# VOLTHAT.net
KiCad netlist of a schematic drawn in EAGLE
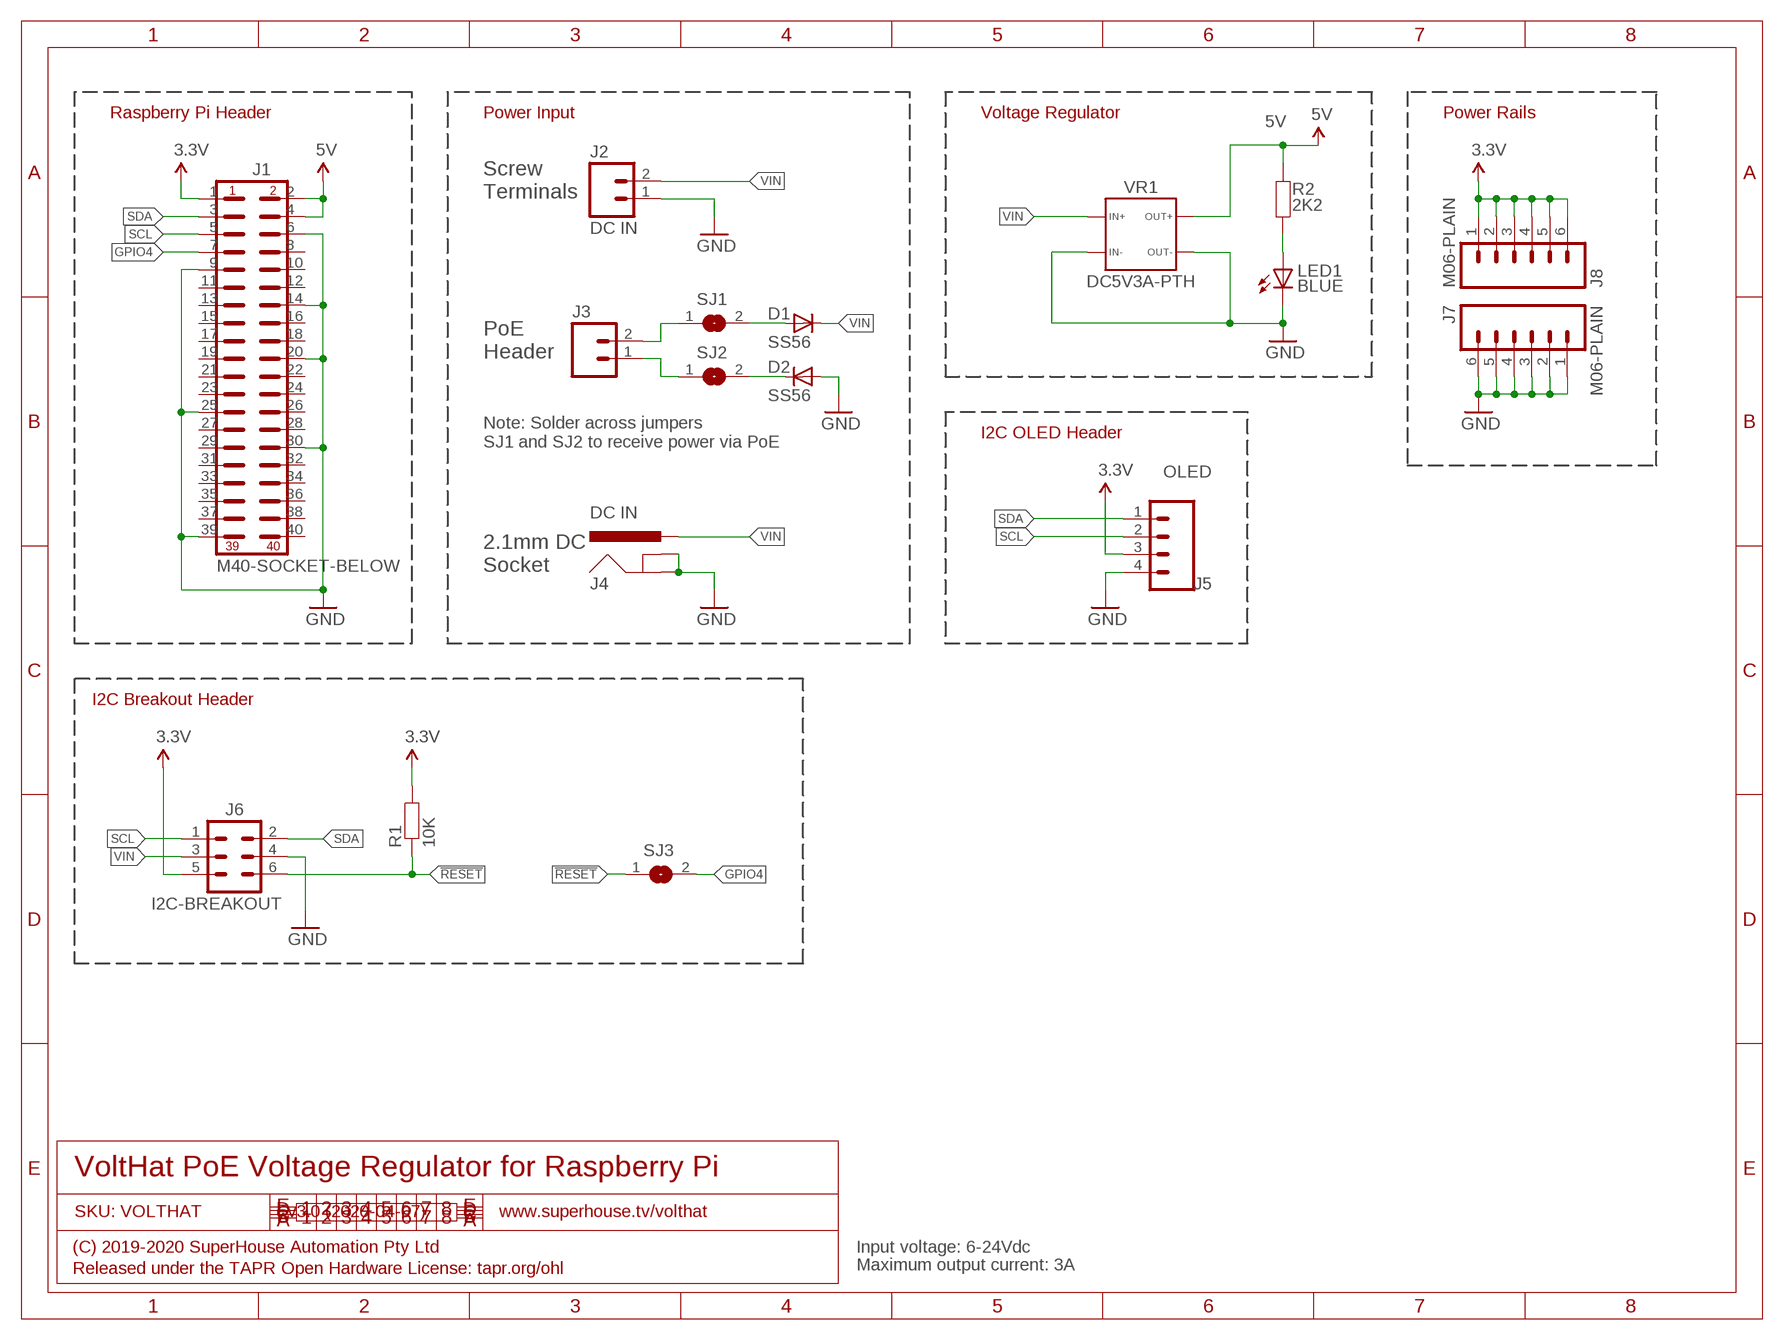
[diagram p0: schematic, sheet 1]

(export (version "E")
  (design (tool "Eeschema 10.0.6"))
  (components
    (comp (ref "D1")
      (value "SS56")
      (footprint "eagle-import:SMA-DIODE")
      (libsource (lib "eagle-import") (part "DIODESMA"))
    )
    (comp (ref "D2")
      (value "SS56")
      (footprint "eagle-import:SMA-DIODE")
      (libsource (lib "eagle-import") (part "DIODESMA"))
    )
    (comp (ref "J1")
      (value "M40-SOCKET-BELOW")
      (footprint "eagle-import:2X20-S-BELOW")
      (libsource (lib "eagle-import") (part "M40-SOCKET-BELOW"))
    )
    (comp (ref "J2")
      (value "DC IN")
      (footprint "eagle-import:SCREWTERMINAL-3.5MM-2")
      (libsource (lib "eagle-import") (part "M02-SCREW-3.5MM"))
    )
    (comp (ref "J3")
      (value "M02-SOCKET-BELOW")
      (footprint "eagle-import:1X02-S-BELOW")
      (libsource (lib "eagle-import") (part "M02-SOCKET-BELOW"))
    )
    (comp (ref "J4")
      (value "DC IN")
      (footprint "eagle-import:POWER_JACK_SLOTS")
      (libsource (lib "eagle-import") (part "POWER_JACK-SLOTS"))
    )
    (comp (ref "J5")
      (value "OLED")
      (footprint "eagle-import:1X04")
      (libsource (lib "eagle-import") (part "M04-PLAIN"))
    )
    (comp (ref "J6")
      (value "I2C-BREAKOUT")
      (footprint "eagle-import:2X03-SHROUDED")
      (libsource (lib "eagle-import") (part "M02X3-SHROUDED"))
    )
    (comp (ref "J7")
      (value "M06-PLAIN")
      (footprint "eagle-import:1X06")
      (libsource (lib "eagle-import") (part "M06-PLAIN"))
    )
    (comp (ref "J8")
      (value "M06-PLAIN")
      (footprint "eagle-import:1X06")
      (libsource (lib "eagle-import") (part "M06-PLAIN"))
    )
    (comp (ref "LED1")
      (value "BLUE")
      (footprint "eagle-import:LED-0603")
      (libsource (lib "eagle-import") (part "LED0603"))
    )
    (comp (ref "R1")
      (value "10K")
      (footprint "eagle-import:R0603")
      (libsource (lib "eagle-import") (part "RESISTOR0603"))
    )
    (comp (ref "R2")
      (value "2K2")
      (footprint "eagle-import:R0603")
      (libsource (lib "eagle-import") (part "RESISTOR0603"))
    )
    (comp (ref "SJ1")
      (value "SJ-NORMAL")
      (footprint "eagle-import:SJ")
      (libsource (lib "eagle-import") (part "SJ-NORMAL"))
    )
    (comp (ref "SJ2")
      (value "SJ-NORMAL")
      (footprint "eagle-import:SJ")
      (libsource (lib "eagle-import") (part "SJ-NORMAL"))
    )
    (comp (ref "SJ3")
      (value "SJ-NORMAL")
      (footprint "eagle-import:SJ")
      (libsource (lib "eagle-import") (part "SJ-NORMAL"))
    )
    (comp (ref "VR1")
      (value "DC5V3A-PTH")
      (footprint "eagle-import:DC5V3A-PTH")
      (libsource (lib "eagle-import") (part "DC5V3A-PTH"))
    )
  )
  (nets
    (net (code "1") (name "/~{RESET}") (class "Default")
      (node (ref "J6") (pin "6") (pinfunction "6_6") (pintype "passive"))
      (node (ref "R1") (pin "1") (pinfunction "1_1") (pintype "passive"))
      (node (ref "SJ3") (pin "1") (pinfunction "1_1") (pintype "passive"))
    )
    (net (code "2") (name "3.3V") (class "Default")
      (node (ref "J1") (pin "1") (pinfunction "1_1") (pintype "passive"))
      (node (ref "J5") (pin "3") (pinfunction "3_3") (pintype "passive"))
      (node (ref "J6") (pin "5") (pinfunction "5_5") (pintype "passive"))
      (node (ref "J8") (pin "1") (pinfunction "1_1") (pintype "passive"))
      (node (ref "J8") (pin "2") (pinfunction "2_2") (pintype "passive"))
      (node (ref "J8") (pin "3") (pinfunction "3_3") (pintype "passive"))
      (node (ref "J8") (pin "4") (pinfunction "4_4") (pintype "passive"))
      (node (ref "J8") (pin "5") (pinfunction "5_5") (pintype "passive"))
      (node (ref "J8") (pin "6") (pinfunction "6_6") (pintype "passive"))
      (node (ref "R1") (pin "2") (pinfunction "2_2") (pintype "passive"))
    )
    (net (code "3") (name "5V") (class "Default")
      (node (ref "J1") (pin "2") (pinfunction "2_2") (pintype "passive"))
      (node (ref "J1") (pin "4") (pinfunction "4_4") (pintype "passive"))
      (node (ref "R2") (pin "1") (pinfunction "1_1") (pintype "passive"))
      (node (ref "VR1") (pin "3A") (pinfunction "3_3A") (pintype "bidirectional"))
      (node (ref "VR1") (pin "3B") (pinfunction "3_3B") (pintype "bidirectional"))
    )
    (net (code "4") (name "GND") (class "Default")
      (node (ref "D2") (pin "A") (pinfunction "A_A") (pintype "passive"))
      (node (ref "J1") (pin "14") (pinfunction "14_14") (pintype "passive"))
      (node (ref "J1") (pin "20") (pinfunction "20_20") (pintype "passive"))
      (node (ref "J1") (pin "25") (pinfunction "25_25") (pintype "passive"))
      (node (ref "J1") (pin "30") (pinfunction "30_30") (pintype "passive"))
      (node (ref "J1") (pin "39") (pinfunction "39_39") (pintype "passive"))
      (node (ref "J1") (pin "6") (pinfunction "6_6") (pintype "passive"))
      (node (ref "J1") (pin "9") (pinfunction "9_9") (pintype "passive"))
      (node (ref "J2") (pin "1") (pinfunction "1_1") (pintype "passive"))
      (node (ref "J4") (pin "GND") (pinfunction "GND_GND") (pintype "bidirectional"))
      (node (ref "J4") (pin "GNDBREAK") (pinfunction "GNDBREAK_GNDBREAK") (pintype "bidirectional"))
      (node (ref "J5") (pin "4") (pinfunction "4_4") (pintype "passive"))
      (node (ref "J6") (pin "4") (pinfunction "4_4") (pintype "passive"))
      (node (ref "J7") (pin "1") (pinfunction "1_1") (pintype "passive"))
      (node (ref "J7") (pin "2") (pinfunction "2_2") (pintype "passive"))
      (node (ref "J7") (pin "3") (pinfunction "3_3") (pintype "passive"))
      (node (ref "J7") (pin "4") (pinfunction "4_4") (pintype "passive"))
      (node (ref "J7") (pin "5") (pinfunction "5_5") (pintype "passive"))
      (node (ref "J7") (pin "6") (pinfunction "6_6") (pintype "passive"))
      (node (ref "LED1") (pin "C") (pinfunction "C_C") (pintype "passive"))
      (node (ref "VR1") (pin "1A") (pinfunction "1_1A") (pintype "bidirectional"))
      (node (ref "VR1") (pin "1B") (pinfunction "1_1B") (pintype "bidirectional"))
      (node (ref "VR1") (pin "4A") (pinfunction "4_4A") (pintype "bidirectional"))
      (node (ref "VR1") (pin "4B") (pinfunction "4_4B") (pintype "bidirectional"))
    )
    (net (code "5") (name "GPIO4") (class "Default")
      (node (ref "J1") (pin "7") (pinfunction "7_7") (pintype "passive"))
      (node (ref "SJ3") (pin "2") (pinfunction "2_2") (pintype "passive"))
    )
    (net (code "6") (name "Net-(D1-PadA)") (class "Default")
      (node (ref "D1") (pin "A") (pinfunction "A_A") (pintype "passive"))
      (node (ref "SJ1") (pin "2") (pinfunction "2_2") (pintype "passive"))
    )
    (net (code "7") (name "Net-(D2-PadC)") (class "Default")
      (node (ref "D2") (pin "C") (pinfunction "C_C") (pintype "passive"))
      (node (ref "SJ2") (pin "2") (pinfunction "2_2") (pintype "passive"))
    )
    (net (code "8") (name "Net-(J3-Pad1)") (class "Default")
      (node (ref "J3") (pin "1") (pinfunction "1_1") (pintype "passive"))
      (node (ref "SJ2") (pin "1") (pinfunction "1_1") (pintype "passive"))
    )
    (net (code "9") (name "Net-(J3-Pad2)") (class "Default")
      (node (ref "J3") (pin "2") (pinfunction "2_2") (pintype "passive"))
      (node (ref "SJ1") (pin "1") (pinfunction "1_1") (pintype "passive"))
    )
    (net (code "10") (name "Net-(LED1-PadA)") (class "Default")
      (node (ref "LED1") (pin "A") (pinfunction "A_A") (pintype "passive"))
      (node (ref "R2") (pin "2") (pinfunction "2_2") (pintype "passive"))
    )
    (net (code "11") (name "SCL") (class "Default")
      (node (ref "J1") (pin "5") (pinfunction "5_5") (pintype "passive"))
      (node (ref "J5") (pin "2") (pinfunction "2_2") (pintype "passive"))
      (node (ref "J6") (pin "1") (pinfunction "1_1") (pintype "passive"))
    )
    (net (code "12") (name "SDA") (class "Default")
      (node (ref "J1") (pin "3") (pinfunction "3_3") (pintype "passive"))
      (node (ref "J5") (pin "1") (pinfunction "1_1") (pintype "passive"))
      (node (ref "J6") (pin "2") (pinfunction "2_2") (pintype "passive"))
    )
    (net (code "13") (name "VIN") (class "Default")
      (node (ref "D1") (pin "C") (pinfunction "C_C") (pintype "passive"))
      (node (ref "J2") (pin "2") (pinfunction "2_2") (pintype "passive"))
      (node (ref "J4") (pin "PWR") (pinfunction "PWR_PWR") (pintype "bidirectional"))
      (node (ref "J6") (pin "3") (pinfunction "3_3") (pintype "passive"))
      (node (ref "VR1") (pin "2A") (pinfunction "2_2A") (pintype "bidirectional"))
      (node (ref "VR1") (pin "2B") (pinfunction "2_2B") (pintype "bidirectional"))
    )
    (net (code "14") (name "unconnected-(J1-Pad8)") (class "Default")
      (node (ref "J1") (pin "8") (pinfunction "8_8") (pintype "passive"))
    )
    (net (code "15") (name "unconnected-(J1-Pad10)") (class "Default")
      (node (ref "J1") (pin "10") (pinfunction "10_10") (pintype "passive"))
    )
    (net (code "16") (name "unconnected-(J1-Pad11)") (class "Default")
      (node (ref "J1") (pin "11") (pinfunction "11_11") (pintype "passive"))
    )
    (net (code "17") (name "unconnected-(J1-Pad12)") (class "Default")
      (node (ref "J1") (pin "12") (pinfunction "12_12") (pintype "passive"))
    )
    (net (code "18") (name "unconnected-(J1-Pad13)") (class "Default")
      (node (ref "J1") (pin "13") (pinfunction "13_13") (pintype "passive"))
    )
    (net (code "19") (name "unconnected-(J1-Pad15)") (class "Default")
      (node (ref "J1") (pin "15") (pinfunction "15_15") (pintype "passive"))
    )
    (net (code "20") (name "unconnected-(J1-Pad16)") (class "Default")
      (node (ref "J1") (pin "16") (pinfunction "16_16") (pintype "passive"))
    )
    (net (code "21") (name "unconnected-(J1-Pad17)") (class "Default")
      (node (ref "J1") (pin "17") (pinfunction "17_17") (pintype "passive"))
    )
    (net (code "22") (name "unconnected-(J1-Pad18)") (class "Default")
      (node (ref "J1") (pin "18") (pinfunction "18_18") (pintype "passive"))
    )
    (net (code "23") (name "unconnected-(J1-Pad19)") (class "Default")
      (node (ref "J1") (pin "19") (pinfunction "19_19") (pintype "passive"))
    )
    (net (code "24") (name "unconnected-(J1-Pad21)") (class "Default")
      (node (ref "J1") (pin "21") (pinfunction "21_21") (pintype "passive"))
    )
    (net (code "25") (name "unconnected-(J1-Pad22)") (class "Default")
      (node (ref "J1") (pin "22") (pinfunction "22_22") (pintype "passive"))
    )
    (net (code "26") (name "unconnected-(J1-Pad23)") (class "Default")
      (node (ref "J1") (pin "23") (pinfunction "23_23") (pintype "passive"))
    )
    (net (code "27") (name "unconnected-(J1-Pad24)") (class "Default")
      (node (ref "J1") (pin "24") (pinfunction "24_24") (pintype "passive"))
    )
    (net (code "28") (name "unconnected-(J1-Pad26)") (class "Default")
      (node (ref "J1") (pin "26") (pinfunction "26_26") (pintype "passive"))
    )
    (net (code "29") (name "unconnected-(J1-Pad27)") (class "Default")
      (node (ref "J1") (pin "27") (pinfunction "27_27") (pintype "passive"))
    )
    (net (code "30") (name "unconnected-(J1-Pad28)") (class "Default")
      (node (ref "J1") (pin "28") (pinfunction "28_28") (pintype "passive"))
    )
    (net (code "31") (name "unconnected-(J1-Pad29)") (class "Default")
      (node (ref "J1") (pin "29") (pinfunction "29_29") (pintype "passive"))
    )
    (net (code "32") (name "unconnected-(J1-Pad31)") (class "Default")
      (node (ref "J1") (pin "31") (pinfunction "31_31") (pintype "passive"))
    )
    (net (code "33") (name "unconnected-(J1-Pad32)") (class "Default")
      (node (ref "J1") (pin "32") (pinfunction "32_32") (pintype "passive"))
    )
    (net (code "34") (name "unconnected-(J1-Pad33)") (class "Default")
      (node (ref "J1") (pin "33") (pinfunction "33_33") (pintype "passive"))
    )
    (net (code "35") (name "unconnected-(J1-Pad34)") (class "Default")
      (node (ref "J1") (pin "34") (pinfunction "34_34") (pintype "passive"))
    )
    (net (code "36") (name "unconnected-(J1-Pad35)") (class "Default")
      (node (ref "J1") (pin "35") (pinfunction "35_35") (pintype "passive"))
    )
    (net (code "37") (name "unconnected-(J1-Pad36)") (class "Default")
      (node (ref "J1") (pin "36") (pinfunction "36_36") (pintype "passive"))
    )
    (net (code "38") (name "unconnected-(J1-Pad37)") (class "Default")
      (node (ref "J1") (pin "37") (pinfunction "37_37") (pintype "passive"))
    )
    (net (code "39") (name "unconnected-(J1-Pad38)") (class "Default")
      (node (ref "J1") (pin "38") (pinfunction "38_38") (pintype "passive"))
    )
    (net (code "40") (name "unconnected-(J1-Pad40)") (class "Default")
      (node (ref "J1") (pin "40") (pinfunction "40_40") (pintype "passive"))
    )
  )
)
